# rgbBreakoutBoard.net
KiCad netlist of a schematic drawn in EAGLE
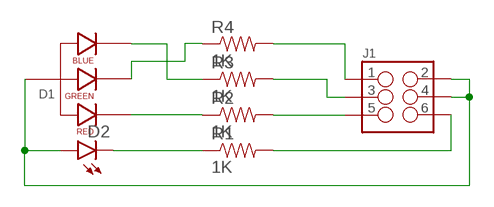
[diagram p0: schematic, sheet 1]

(export (version "E")
  (design (tool "Eeschema 10.0.6"))
  (components
    (comp (ref "D1")
      (value "LED-RGB-CA-THRUCLEAR")
      (footprint "eagle-import:LED-RGB-THRU")
      (libsource (lib "eagle-import") (part "LED-RGB-CA-THRUCLEAR"))
    )
    (comp (ref "D2")
      (value "LED5MM")
      (footprint "eagle-import:LED5MM")
      (libsource (lib "eagle-import") (part "LED5MM"))
    )
    (comp (ref "J1")
      (value "M03X2SMT")
      (footprint "eagle-import:2X3_SMT_POSTS")
      (libsource (lib "eagle-import") (part "M03X2SMT"))
    )
    (comp (ref "R1")
      (value "1K")
      (footprint "eagle-import:0603-RES")
      (libsource (lib "eagle-import") (part "1MOHM-1/10W-1%(0603)"))
    )
    (comp (ref "R2")
      (value "1K")
      (footprint "eagle-import:0603-RES")
      (libsource (lib "eagle-import") (part "1MOHM-1/10W-1%(0603)"))
    )
    (comp (ref "R3")
      (value "1K")
      (footprint "eagle-import:0603-RES")
      (libsource (lib "eagle-import") (part "1MOHM-1/10W-1%(0603)"))
    )
    (comp (ref "R4")
      (value "1K")
      (footprint "eagle-import:0603-RES")
      (libsource (lib "eagle-import") (part "1MOHM-1/10W-1%(0603)"))
    )
  )
  (nets
    (net (code "1") (name "Net-(D1-ANODE)") (class "Default")
      (node (ref "D1") (pin "2") (pinfunction "ANODE_2") (pintype "bidirectional"))
      (node (ref "D2") (pin "A") (pinfunction "A_A") (pintype "passive"))
      (node (ref "J1") (pin "2") (pinfunction "2_2") (pintype "bidirectional"))
      (node (ref "J1") (pin "4") (pinfunction "4_4") (pintype "bidirectional"))
    )
    (net (code "2") (name "Net-(D1-BLUE_CATHODE)") (class "Default")
      (node (ref "D1") (pin "4") (pinfunction "BLUE_CATHODE_4") (pintype "bidirectional"))
      (node (ref "R3") (pin "1") (pinfunction "1_1") (pintype "passive"))
    )
    (net (code "3") (name "Net-(D1-GREEN_CATHODE)") (class "Default")
      (node (ref "D1") (pin "3") (pinfunction "GREEN_CATHODE_3") (pintype "bidirectional"))
      (node (ref "R4") (pin "1") (pinfunction "1_1") (pintype "passive"))
    )
    (net (code "4") (name "Net-(D1-RED_CATHODE)") (class "Default")
      (node (ref "D1") (pin "1") (pinfunction "RED_CATHODE_1") (pintype "bidirectional"))
      (node (ref "R2") (pin "1") (pinfunction "1_1") (pintype "passive"))
    )
    (net (code "5") (name "Net-(D2-C)") (class "Default")
      (node (ref "D2") (pin "K") (pinfunction "C_K") (pintype "passive"))
      (node (ref "R1") (pin "1") (pinfunction "1_1") (pintype "passive"))
    )
    (net (code "6") (name "Net-(J1-Pad1)") (class "Default")
      (node (ref "J1") (pin "1") (pinfunction "1_1") (pintype "bidirectional"))
      (node (ref "R4") (pin "2") (pinfunction "2_2") (pintype "passive"))
    )
    (net (code "7") (name "Net-(J1-Pad3)") (class "Default")
      (node (ref "J1") (pin "3") (pinfunction "3_3") (pintype "bidirectional"))
      (node (ref "R3") (pin "2") (pinfunction "2_2") (pintype "passive"))
    )
    (net (code "8") (name "Net-(J1-Pad5)") (class "Default")
      (node (ref "J1") (pin "5") (pinfunction "5_5") (pintype "bidirectional"))
      (node (ref "R2") (pin "2") (pinfunction "2_2") (pintype "passive"))
    )
    (net (code "9") (name "Net-(J1-Pad6)") (class "Default")
      (node (ref "J1") (pin "6") (pinfunction "6_6") (pintype "bidirectional"))
      (node (ref "R1") (pin "2") (pinfunction "2_2") (pintype "passive"))
    )
  )
)
